# Sheet1.net
KiCad netlist of a schematic drawn in Altium Designer
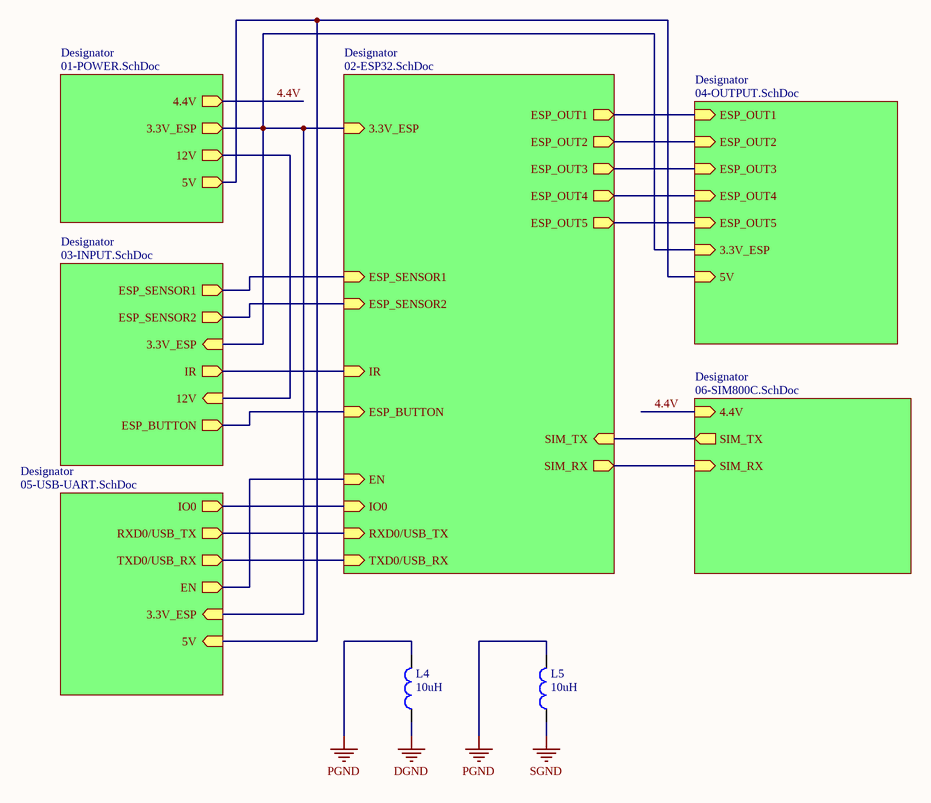
[diagram p0: Sheet1.SchDoc]

(export (version "E")
  (design (tool "Eeschema 10.0.6"))
  (components
    (comp (ref "L4")
      (value "10uH")
      (footprint "L 2520mm")
      (description "Inductor")
      (libsource (lib "lpson") (part "L1"))
    )
    (comp (ref "L5")
      (value "10uH")
      (footprint "L 2520mm")
      (description "Inductor")
      (libsource (lib "lpson") (part "L1"))
    )
  )
  (nets
    (net (code "20") (name "DGND") (class "Default")
      (node (ref "L4") (pin "1") (pinfunction "1_1") (pintype "passive"))
    )
    (net (code "21") (name "PGND") (class "Default")
      (node (ref "L4") (pin "2") (pinfunction "2_2") (pintype "passive"))
      (node (ref "L5") (pin "2") (pinfunction "2_2") (pintype "passive"))
    )
    (net (code "22") (name "SGND") (class "Default")
      (node (ref "L5") (pin "1") (pinfunction "1_1") (pintype "passive"))
    )
  )
)
